# Module.net
KiCad netlist of a schematic drawn in Altium Designer
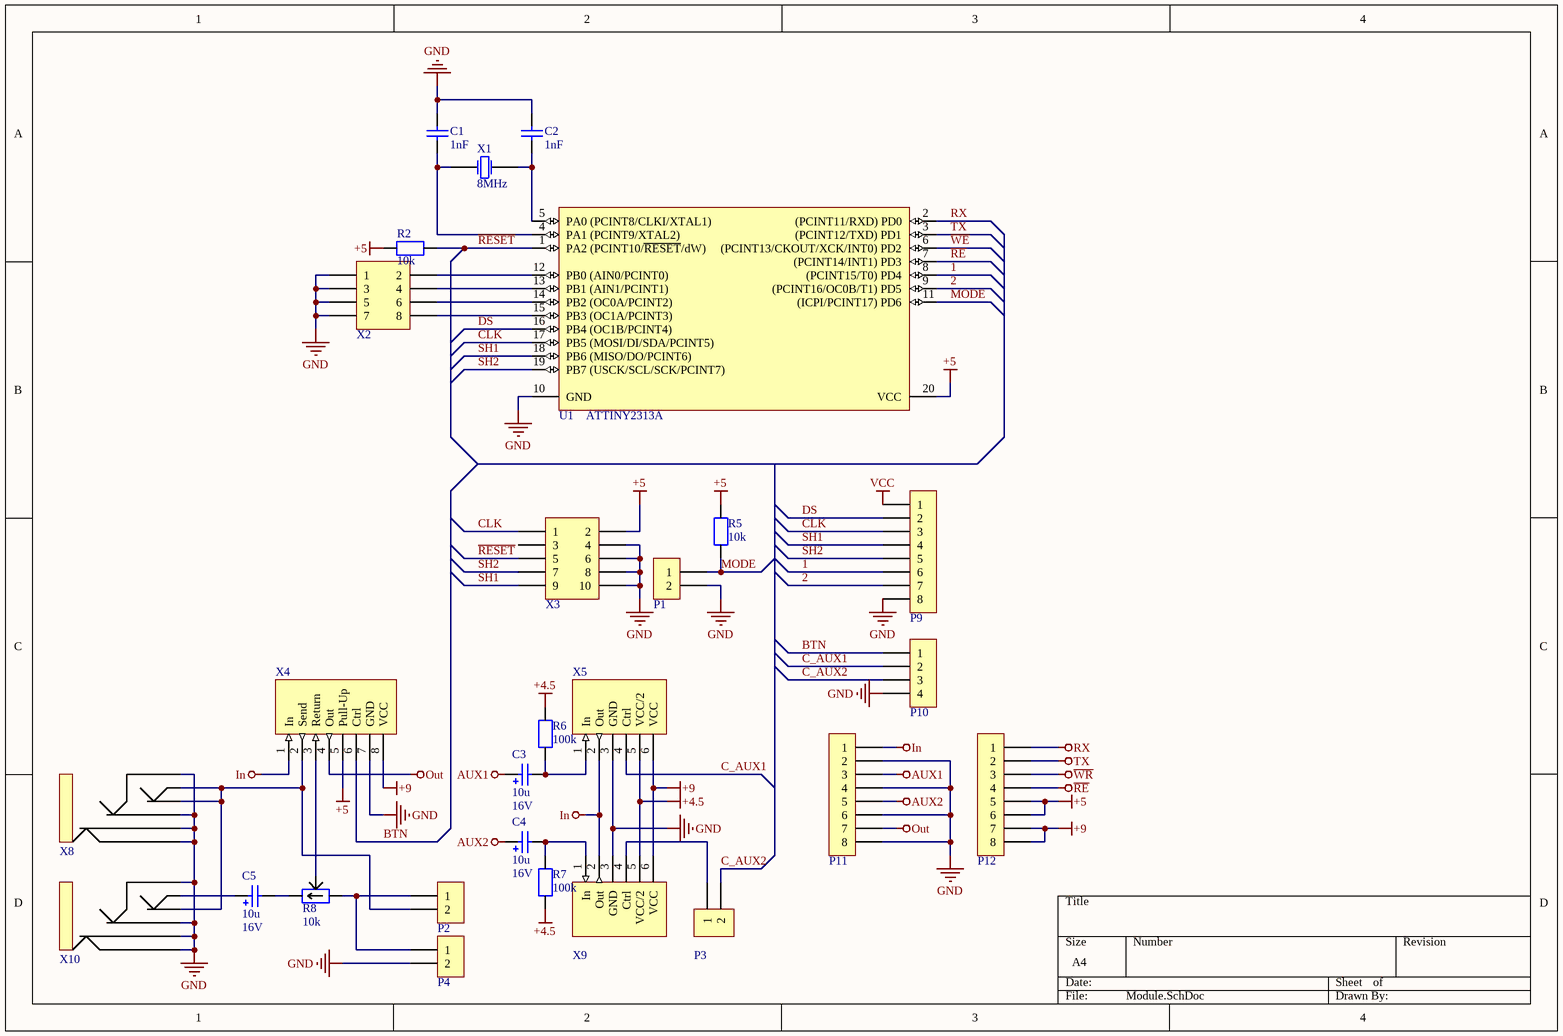
[diagram p0: Module.SchDoc]

(export (version "E")
  (design (tool "Eeschema 10.0.6"))
  (components
    (comp (ref "C1")
      (value "1nF")
      (footprint "0805_Capacitor")
      (fields (field (name "Comment") "Capacitor"))
      (libsource (lib "SchLib1") (part "Capacitor"))
    )
    (comp (ref "C2")
      (value "1nF")
      (footprint "0805_Capacitor")
      (fields (field (name "Comment") "Capacitor"))
      (libsource (lib "SchLib1") (part "Capacitor"))
    )
    (comp (ref "C3")
      (value "10u")
      (footprint "ELEC_RAD10")
      (fields (field (name "INITIAL VOLTAGE") "16V") (field (name "Comment") "Electrolytic Capacitor"))
      (libsource (lib "SchLib1") (part "Electrolytic Capacitor"))
    )
    (comp (ref "C4")
      (value "10u")
      (footprint "ELEC_RAD10")
      (fields (field (name "INITIAL VOLTAGE") "16V") (field (name "Comment") "Electrolytic Capacitor"))
      (libsource (lib "SchLib1") (part "Electrolytic Capacitor"))
    )
    (comp (ref "C5")
      (value "10u")
      (footprint "ELEC_RAD10")
      (fields (field (name "INITIAL VOLTAGE") "16V") (field (name "Comment") "Electrolytic Capacitor"))
      (libsource (lib "SchLib1") (part "Electrolytic Capacitor"))
    )
    (comp (ref "P1")
      (value "SIL-CONN-2")
      (footprint "SIL-CONN-2-jumper")
      (libsource (lib "SchLib1") (part "SIL-CONN-2"))
    )
    (comp (ref "P2")
      (value "SIL-CONN-2")
      (footprint "SIL-CONN-2-jumper")
      (libsource (lib "") (part "SIL-CONN-2_1"))
    )
    (comp (ref "P3")
      (value "SIL-CONN-2")
      (footprint "SIL-CONN-2-jumper")
      (libsource (lib "") (part "SIL-CONN-2_2"))
    )
    (comp (ref "P4")
      (value "SIL-CONN-2")
      (footprint "SIL-CONN-2-jumper")
      (libsource (lib "") (part "SIL-CONN-2_1"))
    )
    (comp (ref "P9")
      (value "SIL-CONN-8")
      (footprint "SIL-CONN-8")
      (libsource (lib "SchLib1") (part "SIL-CONN-8"))
    )
    (comp (ref "P10")
      (value "SIL-CONN-4")
      (footprint "SIL-CONN-4")
      (libsource (lib "SchLib1") (part "SIL-CONN-4"))
    )
    (comp (ref "P11")
      (value "SIL-CONN-8")
      (footprint "SIL-CONN-8")
      (libsource (lib "") (part "SIL-CONN-8_1"))
    )
    (comp (ref "P12")
      (value "SIL-CONN-8")
      (footprint "SIL-CONN-8")
      (libsource (lib "") (part "SIL-CONN-8_1"))
    )
    (comp (ref "R2")
      (value "10k")
      (footprint "0805_Resistor")
      (fields (field (name "Comment") "Resistor"))
      (libsource (lib "SchLib1") (part "Resistor"))
    )
    (comp (ref "R5")
      (value "10k")
      (footprint "0805_Resistor")
      (fields (field (name "Comment") "Resistor"))
      (libsource (lib "") (part "Resistor_1"))
    )
    (comp (ref "R6")
      (value "100k")
      (footprint "0805_Resistor")
      (fields (field (name "Comment") "Resistor"))
      (libsource (lib "") (part "Resistor_1"))
    )
    (comp (ref "R7")
      (value "100k")
      (footprint "0805_Resistor")
      (fields (field (name "Comment") "Resistor"))
      (libsource (lib "") (part "Resistor_1"))
    )
    (comp (ref "R8")
      (value "10k")
      (footprint "Variable Resistor")
      (fields (field (name "Comment") "Variable Resistor"))
      (libsource (lib "SchLib1") (part "Variable Resistor"))
    )
    (comp (ref "U1")
      (value "ATTINY2313A")
      (footprint "SOIC20")
      (libsource (lib "SchLib1") (part "ATTINY2313A"))
    )
    (comp (ref "X1")
      (value "Crystal")
      (footprint "HC49")
      (fields (field (name "FREQUENCY") "8MHz"))
      (libsource (lib "SchLib1") (part "Crystal"))
    )
    (comp (ref "X2")
      (value "DIL-CONN-8")
      (footprint "DIL-CONN-IDC-8")
      (libsource (lib "SchLib1") (part "DIL-CONN-8"))
    )
    (comp (ref "X3")
      (value "DIL-CONN-10")
      (footprint "DIL-CONN-IDC-10")
      (libsource (lib "SchLib1") (part "DIL-CONN-10"))
    )
    (comp (ref "X4")
      (value "MOSFET_Switch_Serial")
      (footprint "MOSFET_Switch_Serial")
      (libsource (lib "SchLib1") (part "MOSFET_Switch_Serial"))
    )
    (comp (ref "X5")
      (value "MOSFET_Switch_Parallel")
      (footprint "MOSFET_Switch_Parallel")
      (libsource (lib "") (part "MOSFET_Switch_Parallel_1"))
    )
    (comp (ref "X8") (value "Jack 6.3") (footprint "Jack 6.3") (libsource (lib "SchLib1") (part "Jack 6.3")))
    (comp (ref "X9")
      (value "MOSFET_Switch_Parallel")
      (footprint "MOSFET_Switch_Parallel")
      (libsource (lib "SchLib1") (part "MOSFET_Switch_Parallel"))
    )
    (comp (ref "X10") (value "Jack 6.3") (footprint "Jack 6.3") (libsource (lib "SchLib1") (part "Jack 6.3")))
  )
  (nets
    (net (code "1") (name "+4.5") (class "Default")
      (node (ref "R6") (pin "2") (pinfunction "2_2") (pintype "passive"))
      (node (ref "R7") (pin "1") (pinfunction "1_1") (pintype "passive"))
      (node (ref "X5") (pin "5") (pinfunction "VCC/2_5") (pintype "power_in"))
      (node (ref "X9") (pin "5") (pinfunction "VCC/2_5") (pintype "power_in"))
    )
    (net (code "2") (name "+5") (class "Default")
      (node (ref "P12") (pin "5") (pinfunction "5_5") (pintype "passive"))
      (node (ref "P12") (pin "6") (pinfunction "6_6") (pintype "passive"))
      (node (ref "R2") (pin "2") (pinfunction "2_2") (pintype "passive"))
      (node (ref "R5") (pin "2") (pinfunction "2_2") (pintype "passive"))
      (node (ref "U1") (pin "20") (pinfunction "VCC_20") (pintype "power_in"))
      (node (ref "X3") (pin "2") (pinfunction "2_2") (pintype "passive"))
      (node (ref "X4") (pin "5") (pinfunction "Pull-Up_5") (pintype "power_in"))
    )
    (net (code "3") (name "+9") (class "Default")
      (node (ref "P12") (pin "7") (pinfunction "7_7") (pintype "passive"))
      (node (ref "P12") (pin "8") (pinfunction "8_8") (pintype "passive"))
      (node (ref "X4") (pin "8") (pinfunction "VCC_8") (pintype "passive"))
      (node (ref "X5") (pin "6") (pinfunction "VCC_6") (pintype "passive"))
      (node (ref "X9") (pin "6") (pinfunction "VCC_6") (pintype "passive"))
    )
    (net (code "4") (name "/1") (class "Default")
      (node (ref "P9") (pin "6") (pinfunction "6_6") (pintype "passive"))
      (node (ref "U1") (pin "8") (pinfunction "(PCINT15/T0)_PD4_8") (pintype "bidirectional"))
    )
    (net (code "5") (name "/2") (class "Default")
      (node (ref "P9") (pin "7") (pinfunction "7_7") (pintype "passive"))
      (node (ref "U1") (pin "9") (pinfunction "(PCINT16/OC0B/T1)_PD5_9") (pintype "bidirectional"))
    )
    (net (code "6") (name "/BTN") (class "Default")
      (node (ref "P10") (pin "1") (pinfunction "1_1") (pintype "passive"))
      (node (ref "X4") (pin "6") (pinfunction "Ctrl_6") (pintype "tri_state"))
    )
    (net (code "7") (name "/CLK") (class "Default")
      (node (ref "P9") (pin "3") (pinfunction "3_3") (pintype "passive"))
      (node (ref "U1") (pin "17") (pinfunction "PB5_(MOSI/DI/SDA/PCINT5)_17") (pintype "bidirectional"))
      (node (ref "X3") (pin "1") (pinfunction "1_1") (pintype "passive"))
    )
    (net (code "8") (name "/C_AUX1") (class "Default")
      (node (ref "P10") (pin "2") (pinfunction "2_2") (pintype "passive"))
      (node (ref "X5") (pin "4") (pinfunction "Ctrl_4") (pintype "tri_state"))
    )
    (net (code "9") (name "/C_AUX2") (class "Default")
      (node (ref "P10") (pin "3") (pinfunction "3_3") (pintype "passive"))
      (node (ref "P3") (pin "2") (pinfunction "2_2") (pintype "passive"))
    )
    (net (code "10") (name "/DS") (class "Default")
      (node (ref "P9") (pin "2") (pinfunction "2_2") (pintype "passive"))
      (node (ref "U1") (pin "16") (pinfunction "PB4_(OC1B/PCINT4)_16") (pintype "bidirectional"))
    )
    (net (code "11") (name "/MODE") (class "Default")
      (node (ref "P1") (pin "1") (pinfunction "1_1") (pintype "passive"))
      (node (ref "R5") (pin "1") (pinfunction "1_1") (pintype "passive"))
      (node (ref "U1") (pin "11") (pinfunction "(ICPI/PCINT17)_PD6_11") (pintype "bidirectional"))
    )
    (net (code "12") (name "/SH1") (class "Default")
      (node (ref "P9") (pin "4") (pinfunction "4_4") (pintype "passive"))
      (node (ref "U1") (pin "18") (pinfunction "PB6_(MISO/DO/PCINT6)_18") (pintype "bidirectional"))
      (node (ref "X3") (pin "9") (pinfunction "9_9") (pintype "passive"))
    )
    (net (code "13") (name "/SH2") (class "Default")
      (node (ref "P9") (pin "5") (pinfunction "5_5") (pintype "passive"))
      (node (ref "U1") (pin "19") (pinfunction "PB7_(USCK/SCL/SCK/PCINT7)_19") (pintype "bidirectional"))
      (node (ref "X3") (pin "7") (pinfunction "7_7") (pintype "passive"))
    )
    (net (code "14") (name "/~{RESET}") (class "Default")
      (node (ref "R2") (pin "1") (pinfunction "1_1") (pintype "passive"))
      (node (ref "U1") (pin "1") (pinfunction "PA2_(PCINT10/~{RESET}/dW)_1") (pintype "bidirectional"))
      (node (ref "X3") (pin "5") (pinfunction "5_5") (pintype "passive"))
    )
    (net (code "15") (name "/~{WE}") (class "Default")
      (node (ref "U1") (pin "6") (pinfunction "(PCINT13/CKOUT/XCK/INT0)_PD2_6") (pintype "bidirectional"))
    )
    (net (code "16") (name "AUX1") (class "Default")
      (node (ref "C3") (pin "+") (pinfunction "+_+") (pintype "passive"))
      (node (ref "P11") (pin "3") (pinfunction "3_3") (pintype "passive"))
    )
    (net (code "17") (name "AUX2") (class "Default")
      (node (ref "C4") (pin "+") (pinfunction "+_+") (pintype "passive"))
      (node (ref "P11") (pin "5") (pinfunction "5_5") (pintype "passive"))
    )
    (net (code "18") (name "GND") (class "Default")
      (node (ref "C1") (pin "2") (pinfunction "2_2") (pintype "passive"))
      (node (ref "C2") (pin "2") (pinfunction "2_2") (pintype "passive"))
      (node (ref "P1") (pin "2") (pinfunction "2_2") (pintype "passive"))
      (node (ref "P10") (pin "4") (pinfunction "4_4") (pintype "passive"))
      (node (ref "P11") (pin "2") (pinfunction "2_2") (pintype "passive"))
      (node (ref "P11") (pin "4") (pinfunction "4_4") (pintype "passive"))
      (node (ref "P11") (pin "6") (pinfunction "6_6") (pintype "passive"))
      (node (ref "P11") (pin "8") (pinfunction "8_8") (pintype "passive"))
      (node (ref "P4") (pin "2") (pinfunction "2_2") (pintype "passive"))
      (node (ref "P9") (pin "8") (pinfunction "8_8") (pintype "passive"))
      (node (ref "U1") (pin "10") (pinfunction "GND_10") (pintype "power_in"))
      (node (ref "X10") (pin "3") (pinfunction "3_3") (pintype "passive"))
      (node (ref "X10") (pin "4") (pinfunction "4_4") (pintype "passive"))
      (node (ref "X10") (pin "5") (pinfunction "5_5") (pintype "passive"))
      (node (ref "X10") (pin "6") (pinfunction "6_6") (pintype "passive"))
      (node (ref "X2") (pin "1") (pinfunction "1_1") (pintype "passive"))
      (node (ref "X2") (pin "3") (pinfunction "3_3") (pintype "passive"))
      (node (ref "X2") (pin "5") (pinfunction "5_5") (pintype "passive"))
      (node (ref "X2") (pin "7") (pinfunction "7_7") (pintype "passive"))
      (node (ref "X3") (pin "10") (pinfunction "10_10") (pintype "passive"))
      (node (ref "X3") (pin "4") (pinfunction "4_4") (pintype "passive"))
      (node (ref "X3") (pin "6") (pinfunction "6_6") (pintype "passive"))
      (node (ref "X3") (pin "8") (pinfunction "8_8") (pintype "passive"))
      (node (ref "X4") (pin "7") (pinfunction "GND_7") (pintype "power_in"))
      (node (ref "X5") (pin "3") (pinfunction "GND_3") (pintype "power_in"))
      (node (ref "X8") (pin "3") (pinfunction "3_3") (pintype "passive"))
      (node (ref "X8") (pin "4") (pinfunction "4_4") (pintype "passive"))
      (node (ref "X8") (pin "5") (pinfunction "5_5") (pintype "passive"))
      (node (ref "X8") (pin "6") (pinfunction "6_6") (pintype "passive"))
      (node (ref "X9") (pin "3") (pinfunction "GND_3") (pintype "power_in"))
    )
    (net (code "19") (name "In") (class "Default")
      (node (ref "P11") (pin "1") (pinfunction "1_1") (pintype "passive"))
      (node (ref "X4") (pin "1") (pinfunction "In_1") (pintype "input"))
      (node (ref "X5") (pin "2") (pinfunction "Out_2") (pintype "output"))
      (node (ref "X9") (pin "2") (pinfunction "Out_2") (pintype "output"))
    )
    (net (code "20") (name "Net-(C5-Pad+)") (class "Default")
      (node (ref "C5") (pin "+") (pinfunction "+_+") (pintype "passive"))
      (node (ref "X10") (pin "1") (pinfunction "1_1") (pintype "passive"))
    )
    (net (code "21") (name "Net-(C5-Pad-)") (class "Default")
      (node (ref "C5") (pin "-") (pinfunction "-_-") (pintype "passive"))
      (node (ref "R8") (pin "2") (pinfunction "2_2") (pintype "passive"))
    )
    (net (code "22") (name "Net-(P2-Pad1)") (class "Default")
      (node (ref "P2") (pin "1") (pinfunction "1_1") (pintype "passive"))
      (node (ref "P4") (pin "1") (pinfunction "1_1") (pintype "passive"))
      (node (ref "R8") (pin "1") (pinfunction "1_1") (pintype "passive"))
    )
    (net (code "23") (name "Net-(U1-PA0_(PCINT8{slash}CLKI{slash}XTAL1))") (class "Default")
      (node (ref "C2") (pin "1") (pinfunction "1_1") (pintype "passive"))
      (node (ref "U1") (pin "5") (pinfunction "PA0_(PCINT8/CLKI/XTAL1)_5") (pintype "bidirectional"))
      (node (ref "X1") (pin "2") (pinfunction "2_2") (pintype "passive"))
    )
    (net (code "24") (name "Net-(U1-PA1_(PCINT9{slash}XTAL2))") (class "Default")
      (node (ref "C1") (pin "1") (pinfunction "1_1") (pintype "passive"))
      (node (ref "U1") (pin "4") (pinfunction "PA1_(PCINT9/XTAL2)_4") (pintype "bidirectional"))
      (node (ref "X1") (pin "1") (pinfunction "1_1") (pintype "passive"))
    )
    (net (code "25") (name "Net-(U1-PB0_(AIN0{slash}PCINT0))") (class "Default")
      (node (ref "U1") (pin "12") (pinfunction "PB0_(AIN0/PCINT0)_12") (pintype "bidirectional"))
      (node (ref "X2") (pin "2") (pinfunction "2_2") (pintype "passive"))
    )
    (net (code "26") (name "Net-(U1-PB1_(AIN1{slash}PCINT1))") (class "Default")
      (node (ref "U1") (pin "13") (pinfunction "PB1_(AIN1/PCINT1)_13") (pintype "bidirectional"))
      (node (ref "X2") (pin "4") (pinfunction "4_4") (pintype "passive"))
    )
    (net (code "27") (name "Net-(U1-PB2_(OC0A{slash}PCINT2))") (class "Default")
      (node (ref "U1") (pin "14") (pinfunction "PB2_(OC0A/PCINT2)_14") (pintype "bidirectional"))
      (node (ref "X2") (pin "6") (pinfunction "6_6") (pintype "passive"))
    )
    (net (code "28") (name "Net-(U1-PB3_(OC1A{slash}PCINT3))") (class "Default")
      (node (ref "U1") (pin "15") (pinfunction "PB3_(OC1A/PCINT3)_15") (pintype "bidirectional"))
      (node (ref "X2") (pin "8") (pinfunction "8_8") (pintype "passive"))
    )
    (net (code "29") (name "Net-(X4-Return)") (class "Default")
      (node (ref "R8") (pin "3") (pinfunction "3_3") (pintype "passive"))
      (node (ref "X4") (pin "3") (pinfunction "Return_3") (pintype "input"))
    )
    (net (code "30") (name "Net-(X4-Send)") (class "Default")
      (node (ref "P2") (pin "2") (pinfunction "2_2") (pintype "passive"))
      (node (ref "X10") (pin "2") (pinfunction "2_2") (pintype "passive"))
      (node (ref "X4") (pin "2") (pinfunction "Send_2") (pintype "output"))
      (node (ref "X8") (pin "1") (pinfunction "1_1") (pintype "passive"))
      (node (ref "X8") (pin "2") (pinfunction "2_2") (pintype "passive"))
    )
    (net (code "31") (name "Net-(X5-In)") (class "Default")
      (node (ref "C3") (pin "-") (pinfunction "-_-") (pintype "passive"))
      (node (ref "R6") (pin "1") (pinfunction "1_1") (pintype "passive"))
      (node (ref "X5") (pin "1") (pinfunction "In_1") (pintype "input"))
    )
    (net (code "32") (name "Net-(X9-Ctrl)") (class "Default")
      (node (ref "P3") (pin "1") (pinfunction "1_1") (pintype "passive"))
      (node (ref "X9") (pin "4") (pinfunction "Ctrl_4") (pintype "tri_state"))
    )
    (net (code "33") (name "Net-(X9-In)") (class "Default")
      (node (ref "C4") (pin "-") (pinfunction "-_-") (pintype "passive"))
      (node (ref "R7") (pin "2") (pinfunction "2_2") (pintype "passive"))
      (node (ref "X9") (pin "1") (pinfunction "In_1") (pintype "input"))
    )
    (net (code "34") (name "Out") (class "Default")
      (node (ref "P11") (pin "7") (pinfunction "7_7") (pintype "passive"))
      (node (ref "X4") (pin "4") (pinfunction "Out_4") (pintype "output"))
    )
    (net (code "35") (name "RX") (class "Default")
      (node (ref "P12") (pin "1") (pinfunction "1_1") (pintype "passive"))
      (node (ref "U1") (pin "2") (pinfunction "(PCINT11/RXD)_PD0_2") (pintype "bidirectional"))
    )
    (net (code "36") (name "TX") (class "Default")
      (node (ref "P12") (pin "2") (pinfunction "2_2") (pintype "passive"))
      (node (ref "U1") (pin "3") (pinfunction "(PCINT12/TXD)_PD1_3") (pintype "bidirectional"))
    )
    (net (code "37") (name "VCC") (class "Default")
      (node (ref "P9") (pin "1") (pinfunction "1_1") (pintype "passive"))
    )
    (net (code "38") (name "unconnected-(X3-Pad3)") (class "Default")
      (node (ref "X3") (pin "3") (pinfunction "3_3") (pintype "passive"))
    )
    (net (code "39") (name "~{RE}") (class "Default")
      (node (ref "P12") (pin "4") (pinfunction "4_4") (pintype "passive"))
      (node (ref "U1") (pin "7") (pinfunction "(PCINT14/INT1)_PD3_7") (pintype "bidirectional"))
    )
    (net (code "40") (name "~{WR}") (class "Default")
      (node (ref "P12") (pin "3") (pinfunction "3_3") (pintype "passive"))
    )
  )
)
